# P10_uSD.net
KiCad netlist of a schematic drawn in Altium Designer
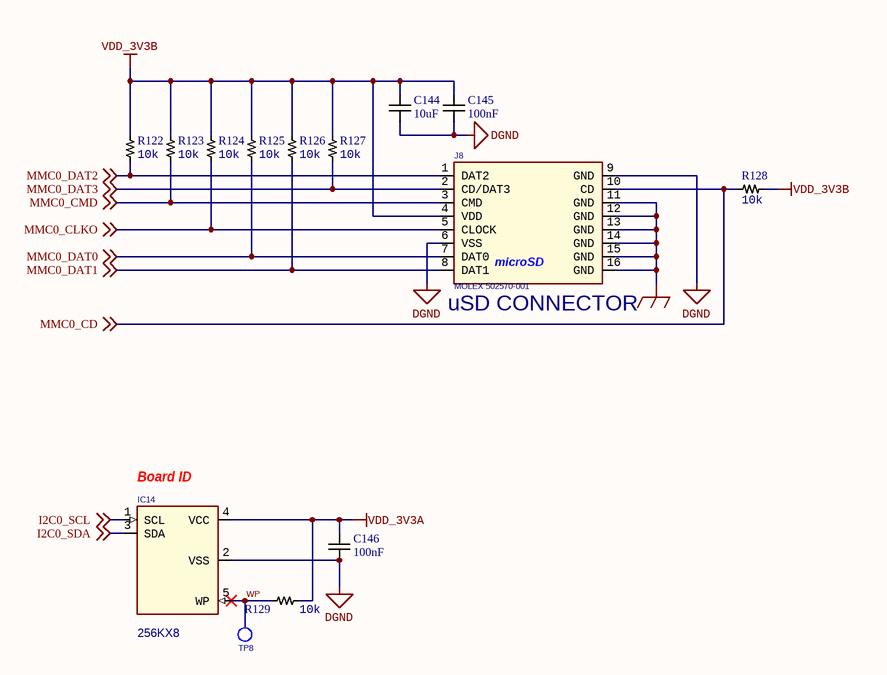
[diagram p0: P10_uSD.SchDoc]

(export (version "E")
  (design (tool "Eeschema 10.0.6"))
  (components
    (comp (ref "C144")
      (value "C2012X6S1A106K085AC")
      (footprint "Orient:CAP0805")
      (description "MLCC 10uF 0805 SMD")
      (fields
        (field (name "CAPACITANCE") "10uF")
        (field (name "MANUFACTURER") "TDK")
        (field (name "TOLERANCE") "10%")
      )
      (libsource (lib "Orient") (part "CAP_10uF"))
    )
    (comp (ref "C145")
      (value "C0402C104K4RACTU")
      (footprint "Orient:CAP0402")
      (description "MLCC 100nF 0402 SMD")
      (fields
        (field (name "MANUFACTURER") "KEMET")
        (field (name "CAPACITANCE") "100nF")
        (field (name "TOLERANCE") "10%")
      )
      (libsource (lib "Orient") (part "CAP_100nF"))
    )
    (comp (ref "C146")
      (value "C0402C104K4RACTU")
      (footprint "Orient:CAP0402")
      (description "MLCC 100nF 0402 SMD")
      (fields
        (field (name "MANUFACTURER") "KEMET")
        (field (name "CAPACITANCE") "100nF")
        (field (name "TOLERANCE") "10%")
      )
      (libsource (lib "Orient") (part "CAP_100nF"))
    )
    (comp (ref "IC14")
      (value "24LC32A")
      (footprint "Orient:SOT-23-5")
      (description "IC EEPROM 32KBIT 400KHZ SOT23-5")
      (fields
        (field (name "MANUFACTURER") "Microchip Technology")
        (field (name "MANUFACTURER PART NUMBER") "24LC32AT-I/OT")
      )
      (libsource (lib "Orient") (part "24LC32A"))
    )
    (comp (ref "J8")
      (value "MOLEX 502570-001")
      (footprint "Orient:SD-MICRO-SCHA5B0300")
      (description "CONN MICRO SD R/A PUSH-PUSH SMD")
      (fields
        (field (name "MANUFACTURER") "Molex Inc")
        (field (name "MANUFACTURER PART NUMBER") "5025700893")
      )
      (libsource (lib "Orient") (part "microSD_CONN_2"))
    )
    (comp (ref "R122")
      (value "RC0402FR-0710KL")
      (footprint "Orient:RES0402")
      (description "Resistor 10kOhm 0402 SMD")
      (fields
        (field (name "MANUFACTURER") "Yageo")
        (field (name "TOLERANCE") "1%")
        (field (name "RESISTANCE") "10k")
      )
      (libsource (lib "Orient") (part "RES_10k"))
    )
    (comp (ref "R123")
      (value "RC0402FR-0710KL")
      (footprint "Orient:RES0402")
      (description "Resistor 10kOhm 0402 SMD")
      (fields
        (field (name "MANUFACTURER") "Yageo")
        (field (name "TOLERANCE") "1%")
        (field (name "RESISTANCE") "10k")
      )
      (libsource (lib "Orient") (part "RES_10k"))
    )
    (comp (ref "R124")
      (value "RC0402FR-0710KL")
      (footprint "Orient:RES0402")
      (description "Resistor 10kOhm 0402 SMD")
      (fields
        (field (name "MANUFACTURER") "Yageo")
        (field (name "TOLERANCE") "1%")
        (field (name "RESISTANCE") "10k")
      )
      (libsource (lib "Orient") (part "RES_10k"))
    )
    (comp (ref "R125")
      (value "RC0402FR-0710KL")
      (footprint "Orient:RES0402")
      (description "Resistor 10kOhm 0402 SMD")
      (fields
        (field (name "MANUFACTURER") "Yageo")
        (field (name "TOLERANCE") "1%")
        (field (name "RESISTANCE") "10k")
      )
      (libsource (lib "Orient") (part "RES_10k"))
    )
    (comp (ref "R126")
      (value "RC0402FR-0710KL")
      (footprint "Orient:RES0402")
      (description "Resistor 10kOhm 0402 SMD")
      (fields
        (field (name "MANUFACTURER") "Yageo")
        (field (name "TOLERANCE") "1%")
        (field (name "RESISTANCE") "10k")
      )
      (libsource (lib "Orient") (part "RES_10k"))
    )
    (comp (ref "R127")
      (value "RC0402FR-0710KL")
      (footprint "Orient:RES0402")
      (description "Resistor 10kOhm 0402 SMD")
      (fields
        (field (name "MANUFACTURER") "Yageo")
        (field (name "TOLERANCE") "1%")
        (field (name "RESISTANCE") "10k")
      )
      (libsource (lib "Orient") (part "RES_10k"))
    )
    (comp (ref "R128")
      (value "RC0402FR-0710KL")
      (footprint "Orient:RES0402")
      (description "Resistor 10kOhm 0402 SMD")
      (fields
        (field (name "MANUFACTURER") "Yageo")
        (field (name "TOLERANCE") "1%")
        (field (name "RESISTANCE") "10k")
      )
      (libsource (lib "Orient") (part "RES_10k"))
    )
    (comp (ref "R129")
      (value "RC0402FR-0710KL")
      (footprint "Orient:RES0402")
      (description "Resistor 10kOhm 0402 SMD")
      (fields
        (field (name "MANUFACTURER") "Yageo")
        (field (name "TOLERANCE") "1%")
        (field (name "RESISTANCE") "10k")
      )
      (libsource (lib "Orient") (part "RES_10k"))
    )
    (comp (ref "TP8")
      (value "TESTPT1")
      (footprint "Orient:tp1-8040")
      (libsource (lib "Orient") (part "TESTPT1"))
    )
  )
  (nets
    (net (code "1") (name "/WP") (class "Default")
      (node (ref "IC14") (pin "5") (pinfunction "WP_5") (pintype "input"))
      (node (ref "R129") (pin "1") (pintype "passive"))
      (node (ref "TP8") (pin "1") (pinfunction "TP_1") (pintype "passive"))
    )
    (net (code "2") (name "DGND") (class "Default")
      (node (ref "C144") (pin "2") (pintype "passive"))
      (node (ref "C145") (pin "2") (pintype "passive"))
      (node (ref "C146") (pin "2") (pintype "passive"))
      (node (ref "IC14") (pin "2") (pinfunction "VSS_2") (pintype "power_in"))
      (node (ref "J8") (pin "6") (pinfunction "VSS_6") (pintype "power_in"))
      (node (ref "J8") (pin "9") (pinfunction "GND_9") (pintype "power_in"))
    )
    (net (code "3") (name "GND_EARTH") (class "Default")
      (node (ref "J8") (pin "11") (pinfunction "GND_11") (pintype "power_in"))
      (node (ref "J8") (pin "12") (pinfunction "GND_12") (pintype "power_in"))
      (node (ref "J8") (pin "13") (pinfunction "GND_13") (pintype "passive"))
      (node (ref "J8") (pin "14") (pinfunction "GND_14") (pintype "passive"))
      (node (ref "J8") (pin "15") (pinfunction "GND_15") (pintype "passive"))
      (node (ref "J8") (pin "16") (pinfunction "GND_16") (pintype "passive"))
    )
    (net (code "4") (name "I2C0_SCL") (class "Default")
      (node (ref "IC14") (pin "1") (pinfunction "SCL_1") (pintype "input"))
    )
    (net (code "5") (name "I2C0_SDA") (class "Default")
      (node (ref "IC14") (pin "3") (pinfunction "SDA_3") (pintype "bidirectional"))
    )
    (net (code "6") (name "MMC0_CD") (class "Default")
      (node (ref "J8") (pin "10") (pinfunction "CD_10") (pintype "passive"))
      (node (ref "R128") (pin "2") (pintype "passive"))
    )
    (net (code "7") (name "MMC0_CLKO") (class "Default")
      (node (ref "J8") (pin "5") (pinfunction "CLOCK_5") (pintype "passive"))
      (node (ref "R124") (pin "1") (pintype "passive"))
    )
    (net (code "8") (name "MMC0_CMD") (class "Default")
      (node (ref "J8") (pin "3") (pinfunction "CMD_3") (pintype "passive"))
      (node (ref "R123") (pin "1") (pintype "passive"))
    )
    (net (code "9") (name "MMC0_DAT0") (class "Default")
      (node (ref "J8") (pin "7") (pinfunction "DAT0_7") (pintype "passive"))
      (node (ref "R125") (pin "1") (pintype "passive"))
    )
    (net (code "10") (name "MMC0_DAT1") (class "Default")
      (node (ref "J8") (pin "8") (pinfunction "DAT1_8") (pintype "passive"))
      (node (ref "R126") (pin "1") (pintype "passive"))
    )
    (net (code "11") (name "MMC0_DAT2") (class "Default")
      (node (ref "J8") (pin "1") (pinfunction "DAT2_1") (pintype "passive"))
      (node (ref "R122") (pin "1") (pintype "passive"))
    )
    (net (code "12") (name "MMC0_DAT3") (class "Default")
      (node (ref "J8") (pin "2") (pinfunction "CD/DAT3_2") (pintype "passive"))
      (node (ref "R127") (pin "1") (pintype "passive"))
    )
    (net (code "13") (name "VDD_3V3A") (class "Default")
      (node (ref "C146") (pin "1") (pintype "passive"))
      (node (ref "IC14") (pin "4") (pinfunction "VCC_4") (pintype "power_in"))
      (node (ref "R129") (pin "2") (pintype "passive"))
    )
    (net (code "14") (name "VDD_3V3B") (class "Default")
      (node (ref "C144") (pin "1") (pintype "passive"))
      (node (ref "C145") (pin "1") (pintype "passive"))
      (node (ref "J8") (pin "4") (pinfunction "VDD_4") (pintype "power_in"))
      (node (ref "R122") (pin "2") (pintype "passive"))
      (node (ref "R123") (pin "2") (pintype "passive"))
      (node (ref "R124") (pin "2") (pintype "passive"))
      (node (ref "R125") (pin "2") (pintype "passive"))
      (node (ref "R126") (pin "2") (pintype "passive"))
      (node (ref "R127") (pin "2") (pintype "passive"))
      (node (ref "R128") (pin "1") (pintype "passive"))
    )
  )
)
